# Slave_l293d.net
KiCad netlist of a schematic drawn in EAGLE
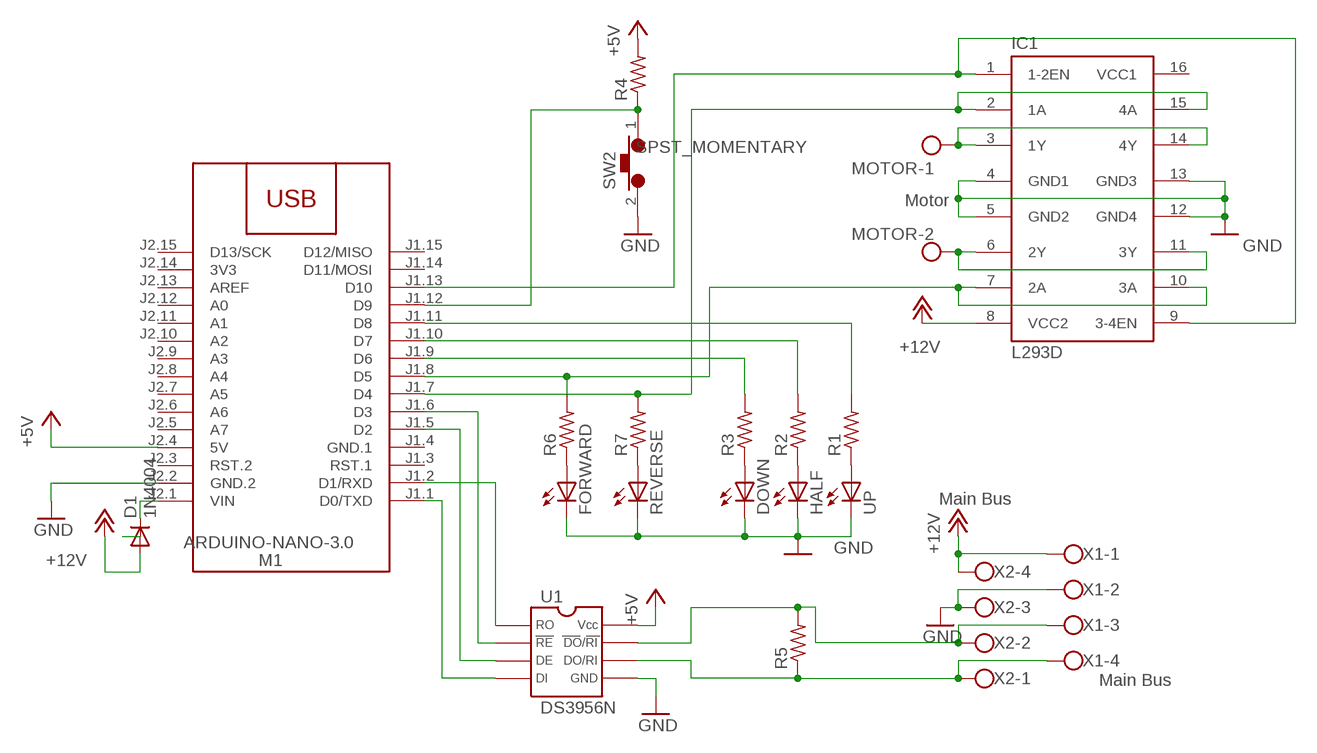
[diagram p0: schematic, sheet 1]

(export (version "E")
  (design (tool "Eeschema 10.0.6"))
  (components
    (comp (ref "D1")
      (value "1N4004")
      (footprint "eagle-import:DO41-10")
      (libsource (lib "eagle-import") (part "1N4004"))
    )
    (comp (ref "DOWN")
      (value "LED5MM")
      (footprint "eagle-import:LED5MM")
      (libsource (lib "eagle-import") (part "LED5MM"))
    )
    (comp (ref "FORWARD")
      (value "LED5MM")
      (footprint "eagle-import:LED5MM")
      (libsource (lib "eagle-import") (part "LED5MM"))
    )
    (comp (ref "HALF")
      (value "LED5MM")
      (footprint "eagle-import:LED5MM")
      (libsource (lib "eagle-import") (part "LED5MM"))
    )
    (comp (ref "IC1")
      (value "L293D")
      (footprint "eagle-import:DIL16")
      (libsource (lib "eagle-import") (part "L293D"))
    )
    (comp (ref "M1")
      (value "ARDUINO-NANO-3.0")
      (footprint "eagle-import:ARDUINO-NANO-3.0")
      (libsource (lib "eagle-import") (part "ARDUINO-NANO-3.0"))
    )
    (comp (ref "MOTOR")
      (value "Motor")
      (footprint "eagle-import:W237-102")
      (fields (field (name "MPN") "237-102"))
      (libsource (lib "eagle-import") (part "W237-102"))
    )
    (comp (ref "R1")
      (value "FLIPFLOP-RES")
      (footprint "eagle-import:0805-THM")
      (libsource (lib "eagle-import") (part "FLIPFLOP-RES"))
    )
    (comp (ref "R2")
      (value "FLIPFLOP-RES")
      (footprint "eagle-import:0805-THM")
      (libsource (lib "eagle-import") (part "FLIPFLOP-RES"))
    )
    (comp (ref "R3")
      (value "FLIPFLOP-RES")
      (footprint "eagle-import:0805-THM")
      (libsource (lib "eagle-import") (part "FLIPFLOP-RES"))
    )
    (comp (ref "R4")
      (value "FLIPFLOP-RES")
      (footprint "eagle-import:0805-THM")
      (libsource (lib "eagle-import") (part "FLIPFLOP-RES"))
    )
    (comp (ref "R5")
      (value "FLIPFLOP-RES")
      (footprint "eagle-import:0805-THM")
      (libsource (lib "eagle-import") (part "FLIPFLOP-RES"))
    )
    (comp (ref "R6")
      (value "FLIPFLOP-RES")
      (footprint "eagle-import:0805-THM")
      (libsource (lib "eagle-import") (part "FLIPFLOP-RES"))
    )
    (comp (ref "R7")
      (value "FLIPFLOP-RES")
      (footprint "eagle-import:0805-THM")
      (libsource (lib "eagle-import") (part "FLIPFLOP-RES"))
    )
    (comp (ref "REVERSE")
      (value "LED5MM")
      (footprint "eagle-import:LED5MM")
      (libsource (lib "eagle-import") (part "LED5MM"))
    )
    (comp (ref "SW2")
      (value "SPST_MOMENTARY")
      (footprint "eagle-import:2PIN")
      (libsource (lib "eagle-import") (part "SPST_MOMENTARY"))
    )
    (comp (ref "U1")
      (value "DS3956N")
      (footprint "eagle-import:DIL08")
      (libsource (lib "eagle-import") (part "DS3956N"))
    )
    (comp (ref "UP")
      (value "LED5MM")
      (footprint "eagle-import:LED5MM")
      (libsource (lib "eagle-import") (part "LED5MM"))
    )
    (comp (ref "X1")
      (value "Main Bus")
      (footprint "eagle-import:W237-4")
      (libsource (lib "eagle-import") (part "W237-4"))
    )
    (comp (ref "X2")
      (value "Main Bus")
      (footprint "eagle-import:W237-4")
      (libsource (lib "eagle-import") (part "W237-4"))
    )
  )
  (nets
    (net (code "1") (name "+5V") (class "Default")
      (node (ref "M1") (pin "J2.4") (pinfunction "5V_J2.4") (pintype "power_in"))
      (node (ref "R4") (pin "2") (pinfunction "2_2") (pintype "passive"))
      (node (ref "U1") (pin "8") (pinfunction "VCC_8") (pintype "bidirectional"))
    )
    (net (code "2") (name "+12V") (class "Default")
      (node (ref "D1") (pin "A") (pinfunction "A_A") (pintype "passive"))
      (node (ref "IC1") (pin "8") (pinfunction "VCC2_8") (pintype "power_in"))
      (node (ref "X1") (pin "1") (pinfunction "KL_1") (pintype "passive"))
      (node (ref "X2") (pin "4") (pinfunction "KL_4") (pintype "passive"))
    )
    (net (code "3") (name "/3V3") (class "Default")
      (node (ref "M1") (pin "J2.14") (pinfunction "3V3_J2.14") (pintype "power_in"))
    )
    (net (code "4") (name "/GND.1") (class "Default")
      (node (ref "M1") (pin "J1.4") (pinfunction "GND.1_J1.4") (pintype "power_in"))
    )
    (net (code "5") (name "/VCC1") (class "Default")
      (node (ref "IC1") (pin "16") (pinfunction "VCC1_16") (pintype "power_in"))
    )
    (net (code "6") (name "GND") (class "Default")
      (node (ref "DOWN") (pin "K") (pinfunction "C_K") (pintype "passive"))
      (node (ref "FORWARD") (pin "K") (pinfunction "C_K") (pintype "passive"))
      (node (ref "HALF") (pin "K") (pinfunction "C_K") (pintype "passive"))
      (node (ref "IC1") (pin "12") (pinfunction "GND4_12") (pintype "power_in"))
      (node (ref "IC1") (pin "13") (pinfunction "GND3_13") (pintype "power_in"))
      (node (ref "IC1") (pin "4") (pinfunction "GND1_4") (pintype "power_in"))
      (node (ref "IC1") (pin "5") (pinfunction "GND2_5") (pintype "power_in"))
      (node (ref "M1") (pin "J2.2") (pinfunction "GND.2_J2.2") (pintype "power_in"))
      (node (ref "REVERSE") (pin "K") (pinfunction "C_K") (pintype "passive"))
      (node (ref "SW2") (pin "2") (pinfunction "P$2_2") (pintype "bidirectional"))
      (node (ref "U1") (pin "5") (pinfunction "GND_5") (pintype "bidirectional"))
      (node (ref "UP") (pin "K") (pinfunction "C_K") (pintype "passive"))
      (node (ref "X1") (pin "2") (pinfunction "KL_2") (pintype "passive"))
      (node (ref "X2") (pin "3") (pinfunction "KL_3") (pintype "passive"))
    )
    (net (code "7") (name "Net-(DOWN-PadA)") (class "Default")
      (node (ref "DOWN") (pin "A") (pinfunction "A_A") (pintype "passive"))
      (node (ref "R3") (pin "1") (pinfunction "1_1") (pintype "passive"))
    )
    (net (code "8") (name "Net-(FORWARD-PadA)") (class "Default")
      (node (ref "FORWARD") (pin "A") (pinfunction "A_A") (pintype "passive"))
      (node (ref "R6") (pin "1") (pinfunction "1_1") (pintype "passive"))
    )
    (net (code "9") (name "Net-(HALF-PadA)") (class "Default")
      (node (ref "HALF") (pin "A") (pinfunction "A_A") (pintype "passive"))
      (node (ref "R2") (pin "1") (pinfunction "1_1") (pintype "passive"))
    )
    (net (code "10") (name "Net-(IC1-1-2EN)") (class "Default")
      (node (ref "IC1") (pin "1") (pinfunction "1-2EN_1") (pintype "input"))
      (node (ref "IC1") (pin "9") (pinfunction "3-4EN_9") (pintype "input"))
      (node (ref "M1") (pin "J1.13") (pinfunction "D10_J1.13") (pintype "bidirectional"))
    )
    (net (code "11") (name "Net-(IC1-1A)") (class "Default")
      (node (ref "IC1") (pin "15") (pinfunction "4A_15") (pintype "input"))
      (node (ref "IC1") (pin "2") (pinfunction "1A_2") (pintype "input"))
      (node (ref "M1") (pin "J1.7") (pinfunction "D4_J1.7") (pintype "bidirectional"))
      (node (ref "R7") (pin "2") (pinfunction "2_2") (pintype "passive"))
    )
    (net (code "12") (name "Net-(IC1-1Y)") (class "Default")
      (node (ref "IC1") (pin "14") (pinfunction "4Y_14") (pintype "output"))
      (node (ref "IC1") (pin "3") (pinfunction "1Y_3") (pintype "output"))
      (node (ref "MOTOR") (pin "1") (pinfunction "KL_1") (pintype "passive"))
    )
    (net (code "13") (name "Net-(IC1-2A)") (class "Default")
      (node (ref "IC1") (pin "10") (pinfunction "3A_10") (pintype "input"))
      (node (ref "IC1") (pin "7") (pinfunction "2A_7") (pintype "input"))
      (node (ref "M1") (pin "J1.8") (pinfunction "D5_J1.8") (pintype "bidirectional"))
      (node (ref "R6") (pin "2") (pinfunction "2_2") (pintype "passive"))
    )
    (net (code "14") (name "Net-(IC1-2Y)") (class "Default")
      (node (ref "IC1") (pin "11") (pinfunction "3Y_11") (pintype "output"))
      (node (ref "IC1") (pin "6") (pinfunction "2Y_6") (pintype "output"))
      (node (ref "MOTOR") (pin "2") (pinfunction "KL_2") (pintype "passive"))
    )
    (net (code "15") (name "Net-(M1-D0{slash}TXD)") (class "Default")
      (node (ref "M1") (pin "J1.1") (pinfunction "D0/TXD_J1.1") (pintype "bidirectional"))
      (node (ref "U1") (pin "4") (pinfunction "DI_4") (pintype "bidirectional"))
    )
    (net (code "16") (name "Net-(M1-D1{slash}RXD)") (class "Default")
      (node (ref "M1") (pin "J1.2") (pinfunction "D1/RXD_J1.2") (pintype "bidirectional"))
      (node (ref "U1") (pin "1") (pinfunction "RO_1") (pintype "bidirectional"))
    )
    (net (code "17") (name "Net-(M1-D2)") (class "Default")
      (node (ref "M1") (pin "J1.5") (pinfunction "D2_J1.5") (pintype "bidirectional"))
      (node (ref "U1") (pin "3") (pinfunction "DE_3") (pintype "bidirectional"))
    )
    (net (code "18") (name "Net-(M1-D3)") (class "Default")
      (node (ref "M1") (pin "J1.6") (pinfunction "D3_J1.6") (pintype "bidirectional"))
      (node (ref "U1") (pin "2") (pinfunction "_RE__2") (pintype "bidirectional"))
    )
    (net (code "19") (name "Net-(M1-D6)") (class "Default")
      (node (ref "M1") (pin "J1.9") (pinfunction "D6_J1.9") (pintype "bidirectional"))
      (node (ref "R3") (pin "2") (pinfunction "2_2") (pintype "passive"))
    )
    (net (code "20") (name "Net-(M1-D7)") (class "Default")
      (node (ref "M1") (pin "J1.10") (pinfunction "D7_J1.10") (pintype "bidirectional"))
      (node (ref "R2") (pin "2") (pinfunction "2_2") (pintype "passive"))
    )
    (net (code "21") (name "Net-(M1-D8)") (class "Default")
      (node (ref "M1") (pin "J1.11") (pinfunction "D8_J1.11") (pintype "bidirectional"))
      (node (ref "R1") (pin "2") (pinfunction "2_2") (pintype "passive"))
    )
    (net (code "22") (name "Net-(M1-D9)") (class "Default")
      (node (ref "M1") (pin "J1.12") (pinfunction "D9_J1.12") (pintype "bidirectional"))
      (node (ref "R4") (pin "1") (pinfunction "1_1") (pintype "passive"))
      (node (ref "SW2") (pin "1") (pinfunction "P$1_1") (pintype "bidirectional"))
    )
    (net (code "23") (name "Net-(M1-VIN)") (class "Default")
      (node (ref "D1") (pin "C") (pinfunction "C_C") (pintype "passive"))
      (node (ref "M1") (pin "J2.1") (pinfunction "VIN_J2.1") (pintype "power_in"))
    )
    (net (code "24") (name "Net-(R1-Pad1)") (class "Default")
      (node (ref "R1") (pin "1") (pinfunction "1_1") (pintype "passive"))
      (node (ref "UP") (pin "A") (pinfunction "A_A") (pintype "passive"))
    )
    (net (code "25") (name "Net-(R7-Pad1)") (class "Default")
      (node (ref "R7") (pin "1") (pinfunction "1_1") (pintype "passive"))
      (node (ref "REVERSE") (pin "A") (pinfunction "A_A") (pintype "passive"))
    )
    (net (code "26") (name "Net-(U1-DO{slash}RI)") (class "Default")
      (node (ref "R5") (pin "1") (pinfunction "1_1") (pintype "passive"))
      (node (ref "U1") (pin "6") (pinfunction "DO/RI_6") (pintype "bidirectional"))
      (node (ref "X1") (pin "4") (pinfunction "KL_4") (pintype "passive"))
      (node (ref "X2") (pin "1") (pinfunction "KL_1") (pintype "passive"))
    )
    (net (code "27") (name "Net-(U1-_DO{slash}RI_)") (class "Default")
      (node (ref "R5") (pin "2") (pinfunction "2_2") (pintype "passive"))
      (node (ref "U1") (pin "7") (pinfunction "_DO/RI__7") (pintype "bidirectional"))
      (node (ref "X1") (pin "3") (pinfunction "KL_3") (pintype "passive"))
      (node (ref "X2") (pin "2") (pinfunction "KL_2") (pintype "passive"))
    )
    (net (code "28") (name "unconnected-(M1-A0-PadJ2.12)") (class "Default")
      (node (ref "M1") (pin "J2.12") (pinfunction "A0_J2.12") (pintype "bidirectional"))
    )
    (net (code "29") (name "unconnected-(M1-A1-PadJ2.11)") (class "Default")
      (node (ref "M1") (pin "J2.11") (pinfunction "A1_J2.11") (pintype "bidirectional"))
    )
    (net (code "30") (name "unconnected-(M1-A2-PadJ2.10)") (class "Default")
      (node (ref "M1") (pin "J2.10") (pinfunction "A2_J2.10") (pintype "bidirectional"))
    )
    (net (code "31") (name "unconnected-(M1-A3-PadJ2.9)") (class "Default")
      (node (ref "M1") (pin "J2.9") (pinfunction "A3_J2.9") (pintype "bidirectional"))
    )
    (net (code "32") (name "unconnected-(M1-A4-PadJ2.8)") (class "Default")
      (node (ref "M1") (pin "J2.8") (pinfunction "A4_J2.8") (pintype "bidirectional"))
    )
    (net (code "33") (name "unconnected-(M1-A5-PadJ2.7)") (class "Default")
      (node (ref "M1") (pin "J2.7") (pinfunction "A5_J2.7") (pintype "bidirectional"))
    )
    (net (code "34") (name "unconnected-(M1-A6-PadJ2.6)") (class "Default")
      (node (ref "M1") (pin "J2.6") (pinfunction "A6_J2.6") (pintype "bidirectional"))
    )
    (net (code "35") (name "unconnected-(M1-A7-PadJ2.5)") (class "Default")
      (node (ref "M1") (pin "J2.5") (pinfunction "A7_J2.5") (pintype "bidirectional"))
    )
    (net (code "36") (name "unconnected-(M1-AREF-PadJ2.13)") (class "Default")
      (node (ref "M1") (pin "J2.13") (pinfunction "AREF_J2.13") (pintype "bidirectional"))
    )
    (net (code "37") (name "unconnected-(M1-D11{slash}MOSI-PadJ1.14)") (class "Default")
      (node (ref "M1") (pin "J1.14") (pinfunction "D11/MOSI_J1.14") (pintype "bidirectional"))
    )
    (net (code "38") (name "unconnected-(M1-D12{slash}MISO-PadJ1.15)") (class "Default")
      (node (ref "M1") (pin "J1.15") (pinfunction "D12/MISO_J1.15") (pintype "bidirectional"))
    )
    (net (code "39") (name "unconnected-(M1-D13{slash}SCK-PadJ2.15)") (class "Default")
      (node (ref "M1") (pin "J2.15") (pinfunction "D13/SCK_J2.15") (pintype "bidirectional"))
    )
    (net (code "40") (name "unconnected-(M1-RST.1-PadJ1.3)") (class "Default")
      (node (ref "M1") (pin "J1.3") (pinfunction "RST.1_J1.3") (pintype "bidirectional"))
    )
    (net (code "41") (name "unconnected-(M1-RST.2-PadJ2.3)") (class "Default")
      (node (ref "M1") (pin "J2.3") (pinfunction "RST.2_J2.3") (pintype "bidirectional"))
    )
  )
)
